# QSTL_24DC_4MW_PCB.net
KiCad netlist of a schematic drawn in Altium Designer
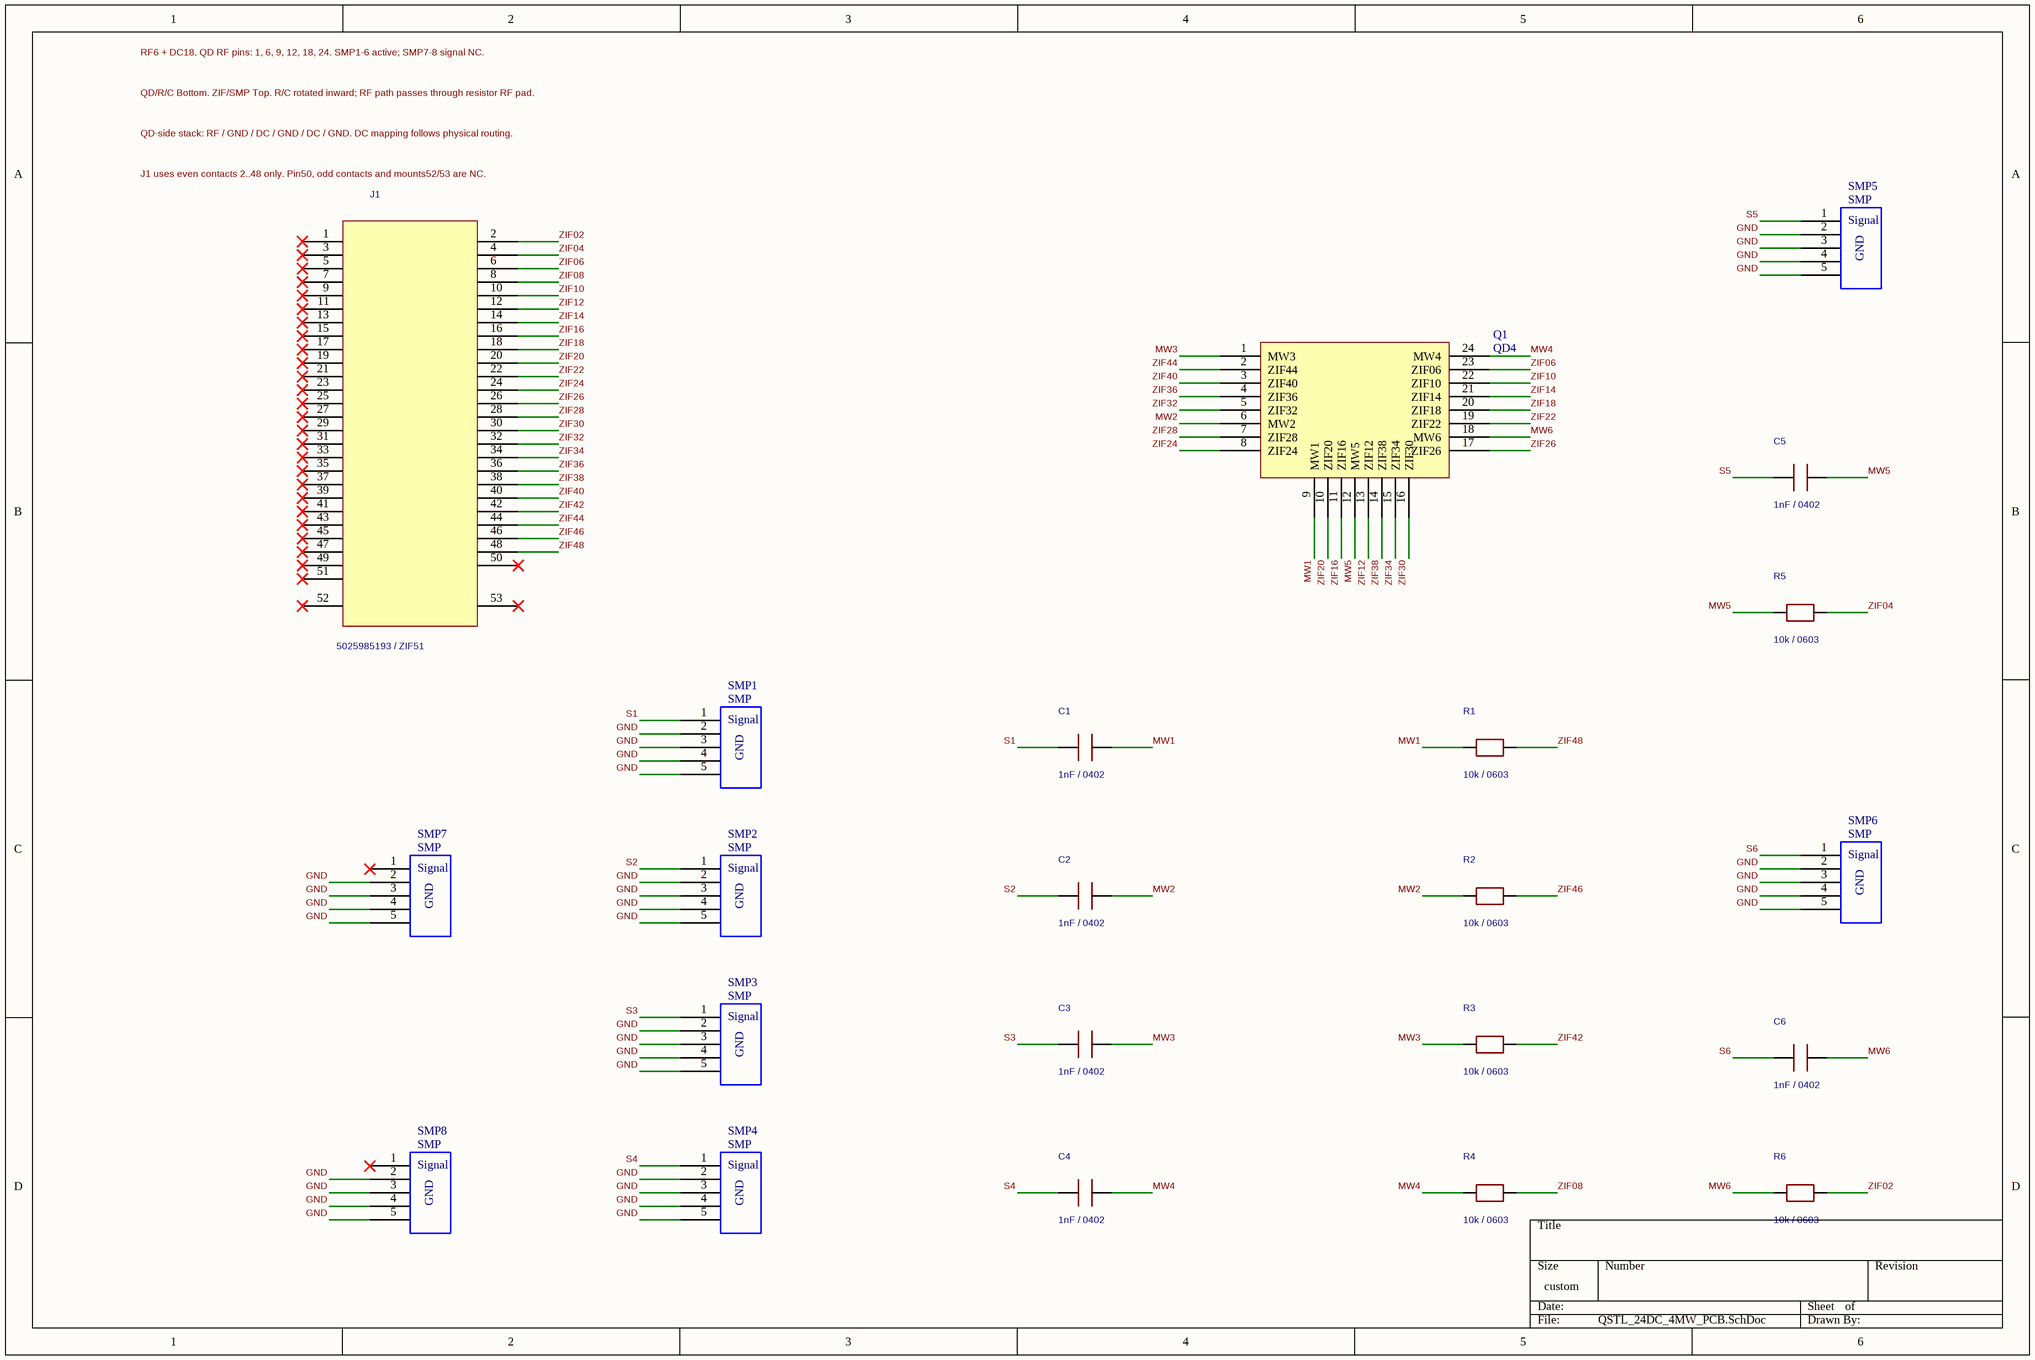
[diagram p0: QSTL_24DC_4MW_PCB.SchDoc]

(export (version "E")
  (design (tool "Eeschema 10.0.6"))
  (components
    (comp (ref "C1")
      (value "1nF / 0402")
      (footprint "Capacitors_0402:FP-GCM155-0_05-IPC_A")
      (description "Ceramic capacitor 1nF 0402; GCM1555C1H102FA16D")
      (libsource (lib "Reference_Capacitors") (part "CMP-06035-056113-1"))
    )
    (comp (ref "C2")
      (value "1nF / 0402")
      (footprint "Capacitors_0402:FP-GCM155-0_05-IPC_A")
      (description "Ceramic capacitor 1nF 0402; GCM1555C1H102FA16D")
      (libsource (lib "Reference_Capacitors") (part "CMP-06035-056113-1"))
    )
    (comp (ref "C3")
      (value "1nF / 0402")
      (footprint "Capacitors_0402:FP-GCM155-0_05-IPC_A")
      (description "Ceramic capacitor 1nF 0402; GCM1555C1H102FA16D")
      (libsource (lib "Reference_Capacitors") (part "CMP-06035-056113-1"))
    )
    (comp (ref "C4")
      (value "1nF / 0402")
      (footprint "Capacitors_0402:FP-GCM155-0_05-IPC_A")
      (description "Ceramic capacitor 1nF 0402; GCM1555C1H102FA16D")
      (libsource (lib "Reference_Capacitors") (part "CMP-06035-056113-1"))
    )
    (comp (ref "C5")
      (value "1nF / 0402")
      (footprint "Capacitors_0402:FP-GCM155-0_05-IPC_A")
      (description "Symmetric placement-only addition; signal pins intentionally unassigned")
      (libsource (lib "Reference_Capacitors") (part "CMP-06035-056113-1"))
    )
    (comp (ref "C6")
      (value "1nF / 0402")
      (footprint "Capacitors_0402:FP-GCM155-0_05-IPC_A")
      (description "Symmetric placement-only addition; signal pins intentionally unassigned")
      (libsource (lib "Reference_Capacitors") (part "CMP-06035-056113-1"))
    )
    (comp (ref "J1")
      (value "5025985193 / ZIF51")
      (footprint "ZIF_5025985193:FP-5025985193-MFG")
      (fields (field (name "MANUFACTURER") "Molex") (field (name "MANUFACTURER PART NUMBER") "5025985193"))
      (libsource (lib "*") (part "ZIF_5025985193_53"))
    )
    (comp (ref "Q1")
      (value "QD4")
      (footprint "QSTL_24DC_4MW_PCB:QD4")
      (description "QD24; RF pins1,6,9,12,18,24; DC18")
      (libsource (lib "QSTL_24DC_4MW_PCB") (part "QD4"))
    )
    (comp (ref "R1")
      (value "10k / 0603")
      (footprint "Passives_0603:CC1608-0603")
      (description "Generic 0603 resistor 10k; value from saved reference schematic")
      (libsource (lib "*") (part "R_0603_10k"))
    )
    (comp (ref "R2")
      (value "10k / 0603")
      (footprint "Passives_0603:CC1608-0603")
      (description "Generic 0603 resistor 10k; value from saved reference schematic")
      (libsource (lib "*") (part "R_0603_10k"))
    )
    (comp (ref "R3")
      (value "10k / 0603")
      (footprint "Passives_0603:CC1608-0603")
      (description "Generic 0603 resistor 10k; value from saved reference schematic")
      (libsource (lib "*") (part "R_0603_10k"))
    )
    (comp (ref "R4")
      (value "10k / 0603")
      (footprint "Passives_0603:CC1608-0603")
      (description "Generic 0603 resistor 10k; value from saved reference schematic")
      (libsource (lib "*") (part "R_0603_10k"))
    )
    (comp (ref "R5")
      (value "10k / 0603")
      (footprint "Passives_0603:CC1608-0603")
      (description "Symmetric placement-only addition; signal pins intentionally unassigned")
      (libsource (lib "*") (part "R_0603_10k"))
    )
    (comp (ref "R6")
      (value "10k / 0603")
      (footprint "Passives_0603:CC1608-0603")
      (description "Symmetric placement-only addition; signal pins intentionally unassigned")
      (libsource (lib "*") (part "R_0603_10k"))
    )
    (comp (ref "SMP1")
      (value "SMP")
      (footprint "Reference_Connectors:RF_Con")
      (libsource (lib "Reference_Connectors") (part "SMP"))
    )
    (comp (ref "SMP2")
      (value "SMP")
      (footprint "Reference_Connectors:RF_Con")
      (libsource (lib "Reference_Connectors") (part "SMP"))
    )
    (comp (ref "SMP3")
      (value "SMP")
      (footprint "Reference_Connectors:RF_Con")
      (libsource (lib "Reference_Connectors") (part "SMP"))
    )
    (comp (ref "SMP4")
      (value "SMP")
      (footprint "Reference_Connectors:RF_Con")
      (libsource (lib "Reference_Connectors") (part "SMP"))
    )
    (comp (ref "SMP5")
      (value "SMP")
      (footprint "Reference_Connectors:RF_Con")
      (description "Symmetric placement-only addition; signal pins intentionally unassigned")
      (libsource (lib "Reference_Connectors") (part "SMP"))
    )
    (comp (ref "SMP6")
      (value "SMP")
      (footprint "Reference_Connectors:RF_Con")
      (description "Symmetric placement-only addition; signal pins intentionally unassigned")
      (libsource (lib "Reference_Connectors") (part "SMP"))
    )
    (comp (ref "SMP7")
      (value "SMP")
      (footprint "Reference_Connectors:RF_Con")
      (description "Restored reference SMP; signal pin1 intentionally NC; shield pins2-5 GND")
      (libsource (lib "Reference_Connectors") (part "SMP"))
    )
    (comp (ref "SMP8")
      (value "SMP")
      (footprint "Reference_Connectors:RF_Con")
      (description "Restored reference SMP; signal pin1 intentionally NC; shield pins2-5 GND")
      (libsource (lib "Reference_Connectors") (part "SMP"))
    )
  )
  (nets
    (net (code "1") (name "/GND") (class "Default")
      (node (ref "SMP1") (pin "2") (pinfunction "2_2") (pintype "passive"))
      (node (ref "SMP1") (pin "3") (pinfunction "3_3") (pintype "passive"))
      (node (ref "SMP1") (pin "4") (pinfunction "4_4") (pintype "passive"))
      (node (ref "SMP1") (pin "5") (pinfunction "5_5") (pintype "passive"))
      (node (ref "SMP2") (pin "2") (pinfunction "2_2") (pintype "passive"))
      (node (ref "SMP2") (pin "3") (pinfunction "3_3") (pintype "passive"))
      (node (ref "SMP2") (pin "4") (pinfunction "4_4") (pintype "passive"))
      (node (ref "SMP2") (pin "5") (pinfunction "5_5") (pintype "passive"))
      (node (ref "SMP3") (pin "2") (pinfunction "2_2") (pintype "passive"))
      (node (ref "SMP3") (pin "3") (pinfunction "3_3") (pintype "passive"))
      (node (ref "SMP3") (pin "4") (pinfunction "4_4") (pintype "passive"))
      (node (ref "SMP3") (pin "5") (pinfunction "5_5") (pintype "passive"))
      (node (ref "SMP4") (pin "2") (pinfunction "2_2") (pintype "passive"))
      (node (ref "SMP4") (pin "3") (pinfunction "3_3") (pintype "passive"))
      (node (ref "SMP4") (pin "4") (pinfunction "4_4") (pintype "passive"))
      (node (ref "SMP4") (pin "5") (pinfunction "5_5") (pintype "passive"))
      (node (ref "SMP5") (pin "2") (pinfunction "2_2") (pintype "passive"))
      (node (ref "SMP5") (pin "3") (pinfunction "3_3") (pintype "passive"))
      (node (ref "SMP5") (pin "4") (pinfunction "4_4") (pintype "passive"))
      (node (ref "SMP5") (pin "5") (pinfunction "5_5") (pintype "passive"))
      (node (ref "SMP6") (pin "2") (pinfunction "2_2") (pintype "passive"))
      (node (ref "SMP6") (pin "3") (pinfunction "3_3") (pintype "passive"))
      (node (ref "SMP6") (pin "4") (pinfunction "4_4") (pintype "passive"))
      (node (ref "SMP6") (pin "5") (pinfunction "5_5") (pintype "passive"))
      (node (ref "SMP7") (pin "2") (pinfunction "2_2") (pintype "passive"))
      (node (ref "SMP7") (pin "3") (pinfunction "3_3") (pintype "passive"))
      (node (ref "SMP7") (pin "4") (pinfunction "4_4") (pintype "passive"))
      (node (ref "SMP7") (pin "5") (pinfunction "5_5") (pintype "passive"))
      (node (ref "SMP8") (pin "2") (pinfunction "2_2") (pintype "passive"))
      (node (ref "SMP8") (pin "3") (pinfunction "3_3") (pintype "passive"))
      (node (ref "SMP8") (pin "4") (pinfunction "4_4") (pintype "passive"))
      (node (ref "SMP8") (pin "5") (pinfunction "5_5") (pintype "passive"))
    )
    (net (code "2") (name "/MW1") (class "Default")
      (node (ref "C1") (pin "2") (pinfunction "2_2") (pintype "passive"))
      (node (ref "Q1") (pin "9") (pinfunction "MW1_9") (pintype "passive"))
      (node (ref "R1") (pin "1") (pinfunction "1_1") (pintype "passive"))
    )
    (net (code "3") (name "/MW2") (class "Default")
      (node (ref "C2") (pin "2") (pinfunction "2_2") (pintype "passive"))
      (node (ref "Q1") (pin "6") (pinfunction "MW2_6") (pintype "passive"))
      (node (ref "R2") (pin "1") (pinfunction "1_1") (pintype "passive"))
    )
    (net (code "4") (name "/MW3") (class "Default")
      (node (ref "C3") (pin "2") (pinfunction "2_2") (pintype "passive"))
      (node (ref "Q1") (pin "1") (pinfunction "MW3_1") (pintype "passive"))
      (node (ref "R3") (pin "1") (pinfunction "1_1") (pintype "passive"))
    )
    (net (code "5") (name "/MW4") (class "Default")
      (node (ref "C4") (pin "2") (pinfunction "2_2") (pintype "passive"))
      (node (ref "Q1") (pin "24") (pinfunction "MW4_24") (pintype "passive"))
      (node (ref "R4") (pin "1") (pinfunction "1_1") (pintype "passive"))
    )
    (net (code "6") (name "/MW5") (class "Default")
      (node (ref "C5") (pin "2") (pinfunction "2_2") (pintype "passive"))
      (node (ref "Q1") (pin "12") (pinfunction "MW5_12") (pintype "passive"))
      (node (ref "R5") (pin "1") (pinfunction "1_1") (pintype "passive"))
    )
    (net (code "7") (name "/MW6") (class "Default")
      (node (ref "C6") (pin "2") (pinfunction "2_2") (pintype "passive"))
      (node (ref "Q1") (pin "18") (pinfunction "MW6_18") (pintype "passive"))
      (node (ref "R6") (pin "1") (pinfunction "1_1") (pintype "passive"))
    )
    (net (code "8") (name "/S1") (class "Default")
      (node (ref "C1") (pin "1") (pinfunction "1_1") (pintype "passive"))
      (node (ref "SMP1") (pin "1") (pinfunction "1_1") (pintype "passive"))
    )
    (net (code "9") (name "/S2") (class "Default")
      (node (ref "C2") (pin "1") (pinfunction "1_1") (pintype "passive"))
      (node (ref "SMP2") (pin "1") (pinfunction "1_1") (pintype "passive"))
    )
    (net (code "10") (name "/S3") (class "Default")
      (node (ref "C3") (pin "1") (pinfunction "1_1") (pintype "passive"))
      (node (ref "SMP3") (pin "1") (pinfunction "1_1") (pintype "passive"))
    )
    (net (code "11") (name "/S4") (class "Default")
      (node (ref "C4") (pin "1") (pinfunction "1_1") (pintype "passive"))
      (node (ref "SMP4") (pin "1") (pinfunction "1_1") (pintype "passive"))
    )
    (net (code "12") (name "/S5") (class "Default")
      (node (ref "C5") (pin "1") (pinfunction "1_1") (pintype "passive"))
      (node (ref "SMP5") (pin "1") (pinfunction "1_1") (pintype "passive"))
    )
    (net (code "13") (name "/S6") (class "Default")
      (node (ref "C6") (pin "1") (pinfunction "1_1") (pintype "passive"))
      (node (ref "SMP6") (pin "1") (pinfunction "1_1") (pintype "passive"))
    )
    (net (code "14") (name "/ZIF02") (class "Default")
      (node (ref "J1") (pin "2") (pinfunction "2_2") (pintype "passive"))
      (node (ref "R6") (pin "2") (pinfunction "2_2") (pintype "passive"))
    )
    (net (code "15") (name "/ZIF04") (class "Default")
      (node (ref "J1") (pin "4") (pinfunction "4_4") (pintype "passive"))
      (node (ref "R5") (pin "2") (pinfunction "2_2") (pintype "passive"))
    )
    (net (code "16") (name "/ZIF06") (class "Default")
      (node (ref "J1") (pin "6") (pinfunction "6_6") (pintype "passive"))
      (node (ref "Q1") (pin "23") (pinfunction "ZIF06_23") (pintype "passive"))
    )
    (net (code "17") (name "/ZIF08") (class "Default")
      (node (ref "J1") (pin "8") (pinfunction "8_8") (pintype "passive"))
      (node (ref "R4") (pin "2") (pinfunction "2_2") (pintype "passive"))
    )
    (net (code "18") (name "/ZIF10") (class "Default")
      (node (ref "J1") (pin "10") (pinfunction "10_10") (pintype "passive"))
      (node (ref "Q1") (pin "22") (pinfunction "ZIF10_22") (pintype "passive"))
    )
    (net (code "19") (name "/ZIF12") (class "Default")
      (node (ref "J1") (pin "12") (pinfunction "12_12") (pintype "passive"))
      (node (ref "Q1") (pin "13") (pinfunction "ZIF12_13") (pintype "passive"))
    )
    (net (code "20") (name "/ZIF14") (class "Default")
      (node (ref "J1") (pin "14") (pinfunction "14_14") (pintype "passive"))
      (node (ref "Q1") (pin "21") (pinfunction "ZIF14_21") (pintype "passive"))
    )
    (net (code "21") (name "/ZIF16") (class "Default")
      (node (ref "J1") (pin "16") (pinfunction "16_16") (pintype "passive"))
      (node (ref "Q1") (pin "11") (pinfunction "ZIF16_11") (pintype "passive"))
    )
    (net (code "22") (name "/ZIF18") (class "Default")
      (node (ref "J1") (pin "18") (pinfunction "18_18") (pintype "passive"))
      (node (ref "Q1") (pin "20") (pinfunction "ZIF18_20") (pintype "passive"))
    )
    (net (code "23") (name "/ZIF20") (class "Default")
      (node (ref "J1") (pin "20") (pinfunction "20_20") (pintype "passive"))
      (node (ref "Q1") (pin "10") (pinfunction "ZIF20_10") (pintype "passive"))
    )
    (net (code "24") (name "/ZIF22") (class "Default")
      (node (ref "J1") (pin "22") (pinfunction "22_22") (pintype "passive"))
      (node (ref "Q1") (pin "19") (pinfunction "ZIF22_19") (pintype "passive"))
    )
    (net (code "25") (name "/ZIF24") (class "Default")
      (node (ref "J1") (pin "24") (pinfunction "24_24") (pintype "passive"))
      (node (ref "Q1") (pin "8") (pinfunction "ZIF24_8") (pintype "passive"))
    )
    (net (code "26") (name "/ZIF26") (class "Default")
      (node (ref "J1") (pin "26") (pinfunction "26_26") (pintype "passive"))
      (node (ref "Q1") (pin "17") (pinfunction "ZIF26_17") (pintype "passive"))
    )
    (net (code "27") (name "/ZIF28") (class "Default")
      (node (ref "J1") (pin "28") (pinfunction "28_28") (pintype "passive"))
      (node (ref "Q1") (pin "7") (pinfunction "ZIF28_7") (pintype "passive"))
    )
    (net (code "28") (name "/ZIF30") (class "Default")
      (node (ref "J1") (pin "30") (pinfunction "30_30") (pintype "passive"))
      (node (ref "Q1") (pin "16") (pinfunction "ZIF30_16") (pintype "passive"))
    )
    (net (code "29") (name "/ZIF32") (class "Default")
      (node (ref "J1") (pin "32") (pinfunction "32_32") (pintype "passive"))
      (node (ref "Q1") (pin "5") (pinfunction "ZIF32_5") (pintype "passive"))
    )
    (net (code "30") (name "/ZIF34") (class "Default")
      (node (ref "J1") (pin "34") (pinfunction "34_34") (pintype "passive"))
      (node (ref "Q1") (pin "15") (pinfunction "ZIF34_15") (pintype "passive"))
    )
    (net (code "31") (name "/ZIF36") (class "Default")
      (node (ref "J1") (pin "36") (pinfunction "36_36") (pintype "passive"))
      (node (ref "Q1") (pin "4") (pinfunction "ZIF36_4") (pintype "passive"))
    )
    (net (code "32") (name "/ZIF38") (class "Default")
      (node (ref "J1") (pin "38") (pinfunction "38_38") (pintype "passive"))
      (node (ref "Q1") (pin "14") (pinfunction "ZIF38_14") (pintype "passive"))
    )
    (net (code "33") (name "/ZIF40") (class "Default")
      (node (ref "J1") (pin "40") (pinfunction "40_40") (pintype "passive"))
      (node (ref "Q1") (pin "3") (pinfunction "ZIF40_3") (pintype "passive"))
    )
    (net (code "34") (name "/ZIF42") (class "Default")
      (node (ref "J1") (pin "42") (pinfunction "42_42") (pintype "passive"))
      (node (ref "R3") (pin "2") (pinfunction "2_2") (pintype "passive"))
    )
    (net (code "35") (name "/ZIF44") (class "Default")
      (node (ref "J1") (pin "44") (pinfunction "44_44") (pintype "passive"))
      (node (ref "Q1") (pin "2") (pinfunction "ZIF44_2") (pintype "passive"))
    )
    (net (code "36") (name "/ZIF46") (class "Default")
      (node (ref "J1") (pin "46") (pinfunction "46_46") (pintype "passive"))
      (node (ref "R2") (pin "2") (pinfunction "2_2") (pintype "passive"))
    )
    (net (code "37") (name "/ZIF48") (class "Default")
      (node (ref "J1") (pin "48") (pinfunction "48_48") (pintype "passive"))
      (node (ref "R1") (pin "2") (pinfunction "2_2") (pintype "passive"))
    )
    (net (code "38") (name "unconnected-(J1-MNT_1-Pad52)") (class "Default")
      (node (ref "J1") (pin "52") (pinfunction "MNT_1_52") (pintype "passive+no_connect"))
    )
    (net (code "39") (name "unconnected-(J1-MNT_2-Pad53)") (class "Default")
      (node (ref "J1") (pin "53") (pinfunction "MNT_2_53") (pintype "passive+no_connect"))
    )
    (net (code "40") (name "unconnected-(J1-Pad1)") (class "Default")
      (node (ref "J1") (pin "1") (pinfunction "1_1") (pintype "passive+no_connect"))
    )
    (net (code "41") (name "unconnected-(J1-Pad3)") (class "Default")
      (node (ref "J1") (pin "3") (pinfunction "3_3") (pintype "passive+no_connect"))
    )
    (net (code "42") (name "unconnected-(J1-Pad5)") (class "Default")
      (node (ref "J1") (pin "5") (pinfunction "5_5") (pintype "passive+no_connect"))
    )
    (net (code "43") (name "unconnected-(J1-Pad7)") (class "Default")
      (node (ref "J1") (pin "7") (pinfunction "7_7") (pintype "passive+no_connect"))
    )
    (net (code "44") (name "unconnected-(J1-Pad9)") (class "Default")
      (node (ref "J1") (pin "9") (pinfunction "9_9") (pintype "passive+no_connect"))
    )
    (net (code "45") (name "unconnected-(J1-Pad11)") (class "Default")
      (node (ref "J1") (pin "11") (pinfunction "11_11") (pintype "passive+no_connect"))
    )
    (net (code "46") (name "unconnected-(J1-Pad13)") (class "Default")
      (node (ref "J1") (pin "13") (pinfunction "13_13") (pintype "passive+no_connect"))
    )
    (net (code "47") (name "unconnected-(J1-Pad15)") (class "Default")
      (node (ref "J1") (pin "15") (pinfunction "15_15") (pintype "passive+no_connect"))
    )
    (net (code "48") (name "unconnected-(J1-Pad17)") (class "Default")
      (node (ref "J1") (pin "17") (pinfunction "17_17") (pintype "passive+no_connect"))
    )
    (net (code "49") (name "unconnected-(J1-Pad19)") (class "Default")
      (node (ref "J1") (pin "19") (pinfunction "19_19") (pintype "passive+no_connect"))
    )
    (net (code "50") (name "unconnected-(J1-Pad21)") (class "Default")
      (node (ref "J1") (pin "21") (pinfunction "21_21") (pintype "passive+no_connect"))
    )
    (net (code "51") (name "unconnected-(J1-Pad23)") (class "Default")
      (node (ref "J1") (pin "23") (pinfunction "23_23") (pintype "passive+no_connect"))
    )
    (net (code "52") (name "unconnected-(J1-Pad25)") (class "Default")
      (node (ref "J1") (pin "25") (pinfunction "25_25") (pintype "passive+no_connect"))
    )
    (net (code "53") (name "unconnected-(J1-Pad27)") (class "Default")
      (node (ref "J1") (pin "27") (pinfunction "27_27") (pintype "passive+no_connect"))
    )
    (net (code "54") (name "unconnected-(J1-Pad29)") (class "Default")
      (node (ref "J1") (pin "29") (pinfunction "29_29") (pintype "passive+no_connect"))
    )
    (net (code "55") (name "unconnected-(J1-Pad31)") (class "Default")
      (node (ref "J1") (pin "31") (pinfunction "31_31") (pintype "passive+no_connect"))
    )
    (net (code "56") (name "unconnected-(J1-Pad33)") (class "Default")
      (node (ref "J1") (pin "33") (pinfunction "33_33") (pintype "passive+no_connect"))
    )
    (net (code "57") (name "unconnected-(J1-Pad35)") (class "Default")
      (node (ref "J1") (pin "35") (pinfunction "35_35") (pintype "passive+no_connect"))
    )
    (net (code "58") (name "unconnected-(J1-Pad37)") (class "Default")
      (node (ref "J1") (pin "37") (pinfunction "37_37") (pintype "passive+no_connect"))
    )
    (net (code "59") (name "unconnected-(J1-Pad39)") (class "Default")
      (node (ref "J1") (pin "39") (pinfunction "39_39") (pintype "passive+no_connect"))
    )
    (net (code "60") (name "unconnected-(J1-Pad41)") (class "Default")
      (node (ref "J1") (pin "41") (pinfunction "41_41") (pintype "passive+no_connect"))
    )
    (net (code "61") (name "unconnected-(J1-Pad43)") (class "Default")
      (node (ref "J1") (pin "43") (pinfunction "43_43") (pintype "passive+no_connect"))
    )
    (net (code "62") (name "unconnected-(J1-Pad45)") (class "Default")
      (node (ref "J1") (pin "45") (pinfunction "45_45") (pintype "passive+no_connect"))
    )
    (net (code "63") (name "unconnected-(J1-Pad47)") (class "Default")
      (node (ref "J1") (pin "47") (pinfunction "47_47") (pintype "passive+no_connect"))
    )
    (net (code "64") (name "unconnected-(J1-Pad49)") (class "Default")
      (node (ref "J1") (pin "49") (pinfunction "49_49") (pintype "passive+no_connect"))
    )
    (net (code "65") (name "unconnected-(J1-Pad50)") (class "Default")
      (node (ref "J1") (pin "50") (pinfunction "50_50") (pintype "passive+no_connect"))
    )
    (net (code "66") (name "unconnected-(J1-Pad51)") (class "Default")
      (node (ref "J1") (pin "51") (pinfunction "51_51") (pintype "passive+no_connect"))
    )
    (net (code "67") (name "unconnected-(SMP7-Pad1)") (class "Default")
      (node (ref "SMP7") (pin "1") (pinfunction "1_1") (pintype "passive+no_connect"))
    )
    (net (code "68") (name "unconnected-(SMP8-Pad1)") (class "Default")
      (node (ref "SMP8") (pin "1") (pinfunction "1_1") (pintype "passive+no_connect"))
    )
  )
)
